# Video_1.net
KiCad netlist of a schematic drawn in EAGLE
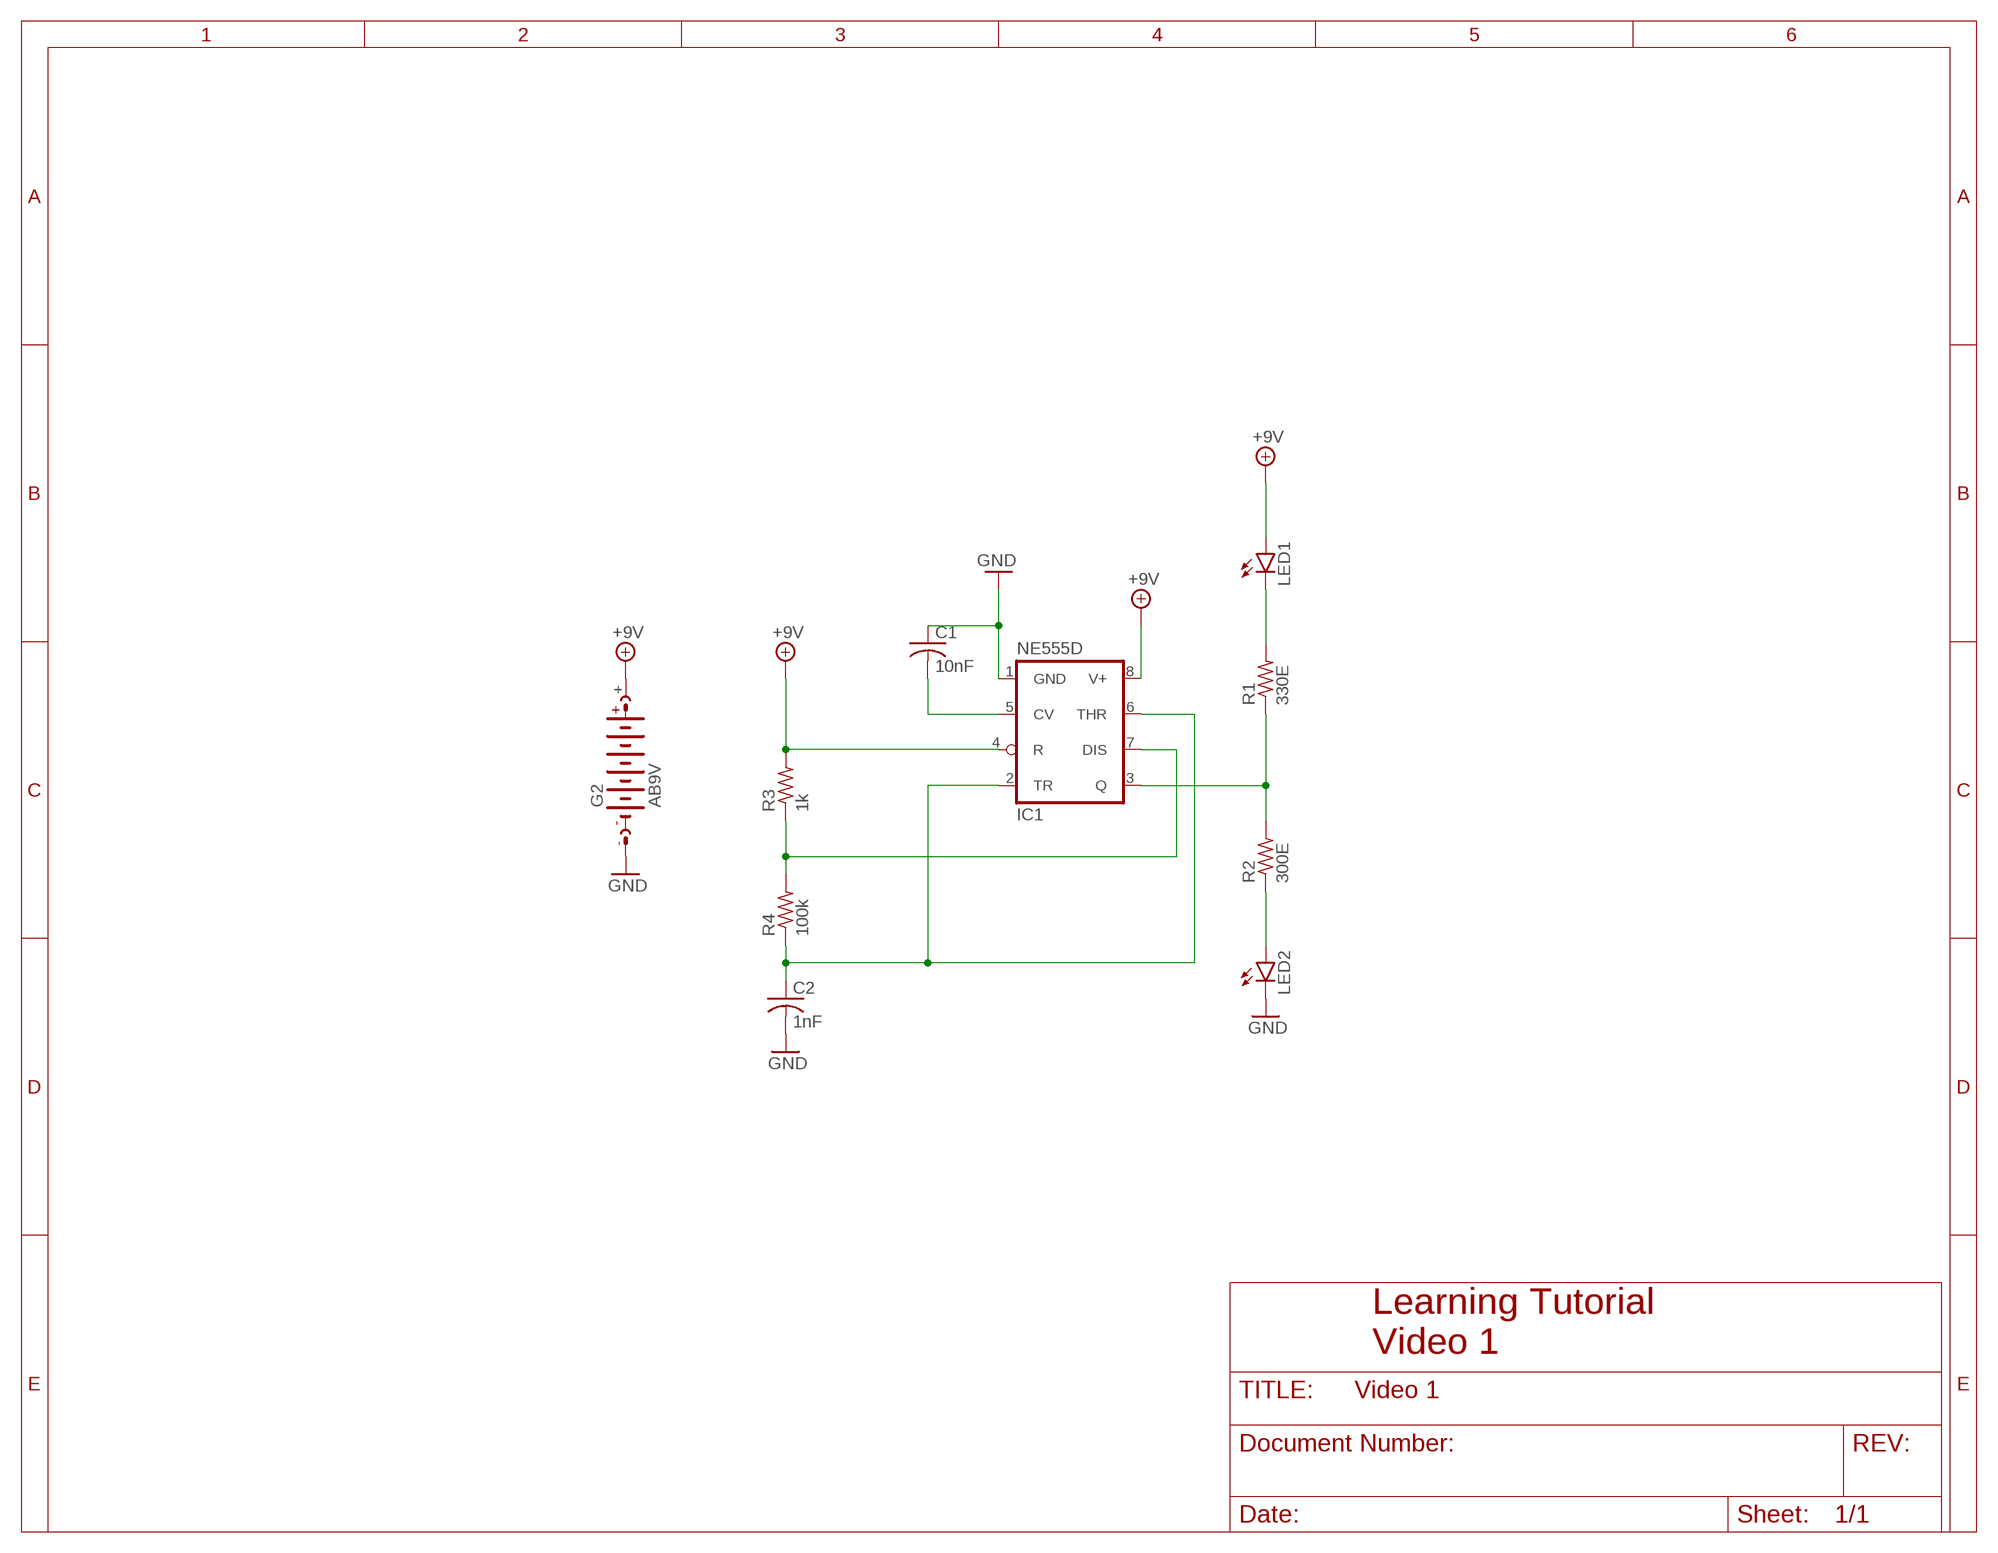
[diagram p0: schematic, sheet 1]

(export (version "E")
  (design (tool "Eeschema 10.0.6"))
  (components
    (comp (ref "C1")
      (value "10nF")
      (footprint "eagle-import:C1206")
      (libsource (lib "eagle-import") (part "C-USC1206"))
    )
    (comp (ref "C2")
      (value "1nF")
      (footprint "eagle-import:C1206")
      (libsource (lib "eagle-import") (part "C-USC1206"))
    )
    (comp (ref "G2")
      (value "AB9V")
      (footprint "eagle-import:AB9V")
      (libsource (lib "eagle-import") (part "AB9V"))
    )
    (comp (ref "IC1")
      (value "NE555D")
      (footprint "eagle-import:SO08")
      (libsource (lib "eagle-import") (part "555DNE"))
    )
    (comp (ref "LED1")
      (value "LED5MM")
      (footprint "eagle-import:LED5MM")
      (libsource (lib "eagle-import") (part "LED5MM"))
    )
    (comp (ref "LED2")
      (value "LED5MM")
      (footprint "eagle-import:LED5MM")
      (libsource (lib "eagle-import") (part "LED5MM"))
    )
    (comp (ref "R1")
      (value "330E")
      (footprint "eagle-import:R0603")
      (libsource (lib "eagle-import") (part "R-US_R0603"))
    )
    (comp (ref "R2")
      (value "300E")
      (footprint "eagle-import:R0603")
      (libsource (lib "eagle-import") (part "R-US_R0603"))
    )
    (comp (ref "R3")
      (value "1k")
      (footprint "eagle-import:R0603")
      (libsource (lib "eagle-import") (part "R-US_R0603"))
    )
    (comp (ref "R4")
      (value "100k")
      (footprint "eagle-import:R0603")
      (libsource (lib "eagle-import") (part "R-US_R0603"))
    )
  )
  (nets
    (net (code "1") (name "+9V") (class "Default")
      (node (ref "G2") (pin "+") (pinfunction "+_+") (pintype "passive"))
      (node (ref "IC1") (pin "4") (pinfunction "R_4") (pintype "input"))
      (node (ref "IC1") (pin "8") (pinfunction "V+_8") (pintype "power_in"))
      (node (ref "LED1") (pin "A") (pinfunction "A_A") (pintype "passive"))
      (node (ref "R3") (pin "2") (pinfunction "2_2") (pintype "passive"))
    )
    (net (code "2") (name "GND") (class "Default")
      (node (ref "C1") (pin "1") (pinfunction "1_1") (pintype "passive"))
      (node (ref "C2") (pin "2") (pinfunction "2_2") (pintype "passive"))
      (node (ref "G2") (pin "-") (pinfunction "-_-") (pintype "passive"))
      (node (ref "IC1") (pin "1") (pinfunction "GND_1") (pintype "power_in"))
      (node (ref "LED2") (pin "K") (pinfunction "C_K") (pintype "passive"))
    )
    (net (code "3") (name "Net-(IC1-CV)") (class "Default")
      (node (ref "C1") (pin "2") (pinfunction "2_2") (pintype "passive"))
      (node (ref "IC1") (pin "5") (pinfunction "CV_5") (pintype "input"))
    )
    (net (code "4") (name "Net-(IC1-DIS)") (class "Default")
      (node (ref "IC1") (pin "7") (pinfunction "DIS_7") (pintype "input"))
      (node (ref "R3") (pin "1") (pinfunction "1_1") (pintype "passive"))
      (node (ref "R4") (pin "2") (pinfunction "2_2") (pintype "passive"))
    )
    (net (code "5") (name "Net-(IC1-Q)") (class "Default")
      (node (ref "IC1") (pin "3") (pinfunction "Q_3") (pintype "output"))
      (node (ref "R1") (pin "1") (pinfunction "1_1") (pintype "passive"))
      (node (ref "R2") (pin "2") (pinfunction "2_2") (pintype "passive"))
    )
    (net (code "6") (name "Net-(IC1-THR)") (class "Default")
      (node (ref "C2") (pin "1") (pinfunction "1_1") (pintype "passive"))
      (node (ref "IC1") (pin "2") (pinfunction "TR_2") (pintype "input"))
      (node (ref "IC1") (pin "6") (pinfunction "THR_6") (pintype "input"))
      (node (ref "R4") (pin "1") (pinfunction "1_1") (pintype "passive"))
    )
    (net (code "7") (name "Net-(LED1-C)") (class "Default")
      (node (ref "LED1") (pin "K") (pinfunction "C_K") (pintype "passive"))
      (node (ref "R1") (pin "2") (pinfunction "2_2") (pintype "passive"))
    )
    (net (code "8") (name "Net-(LED2-PadA)") (class "Default")
      (node (ref "LED2") (pin "A") (pinfunction "A_A") (pintype "passive"))
      (node (ref "R2") (pin "1") (pinfunction "1_1") (pintype "passive"))
    )
  )
)
